# RetroESP32.net
KiCad netlist of a schematic drawn in EAGLE
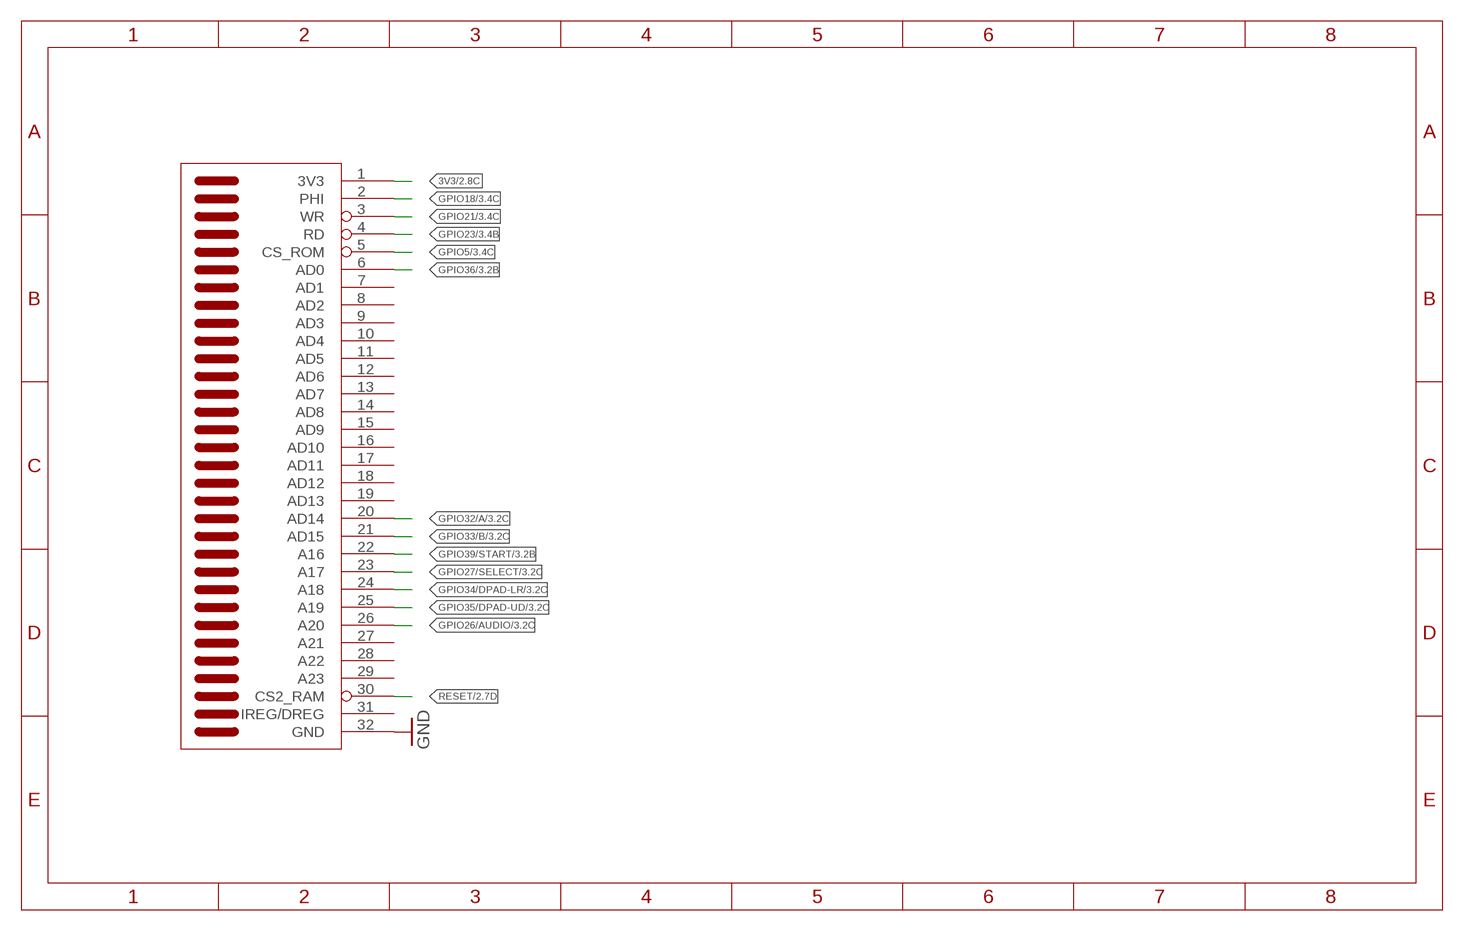
[diagram p0: schematic, sheet 1]
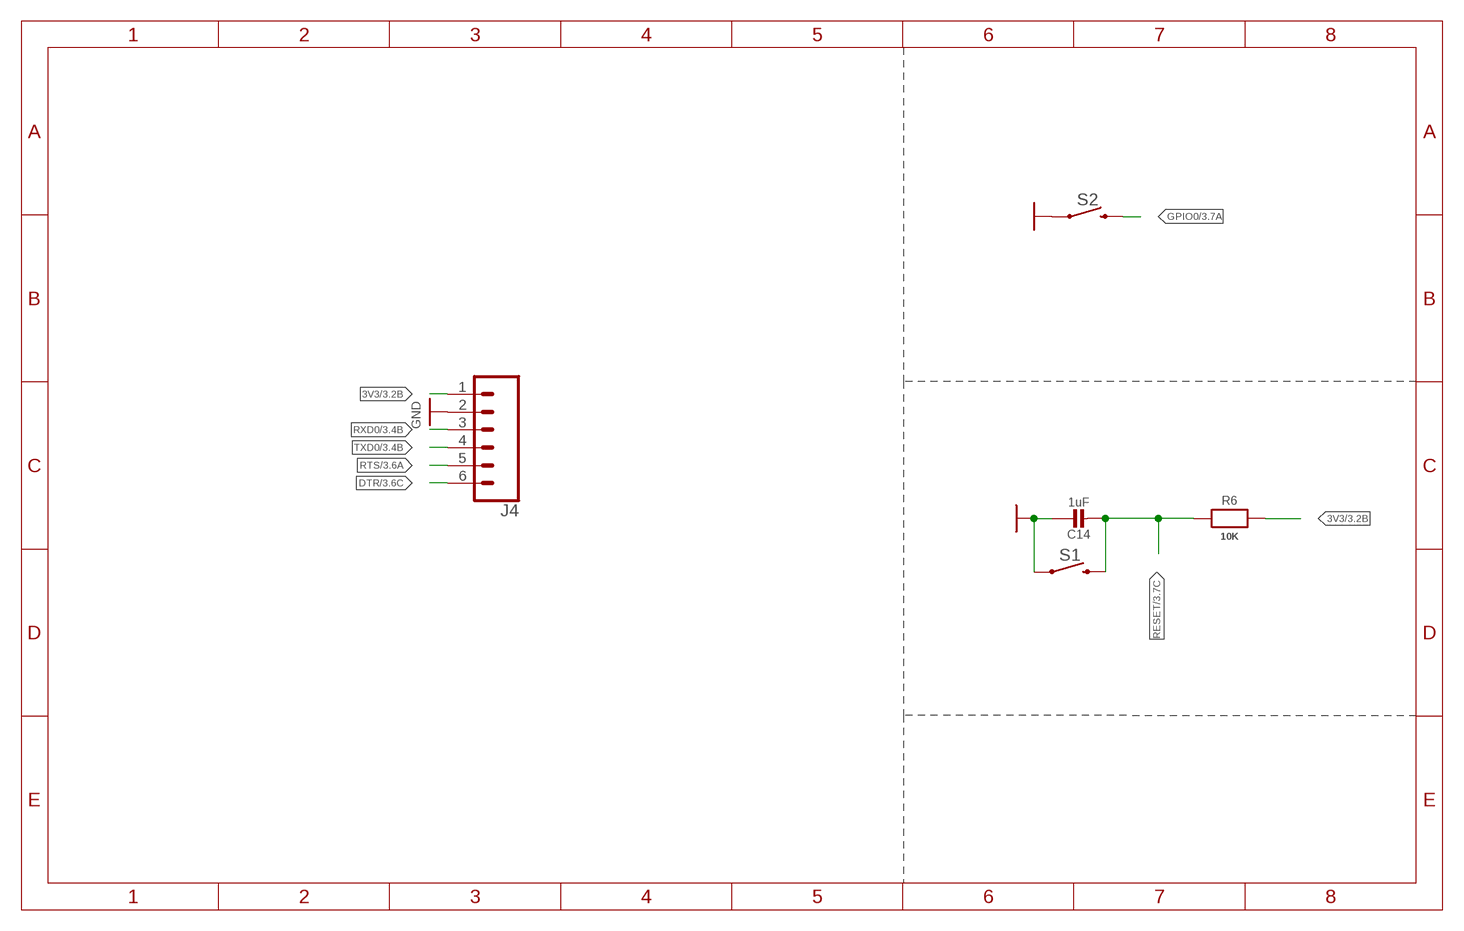
[diagram p1: schematic, sheet 2]
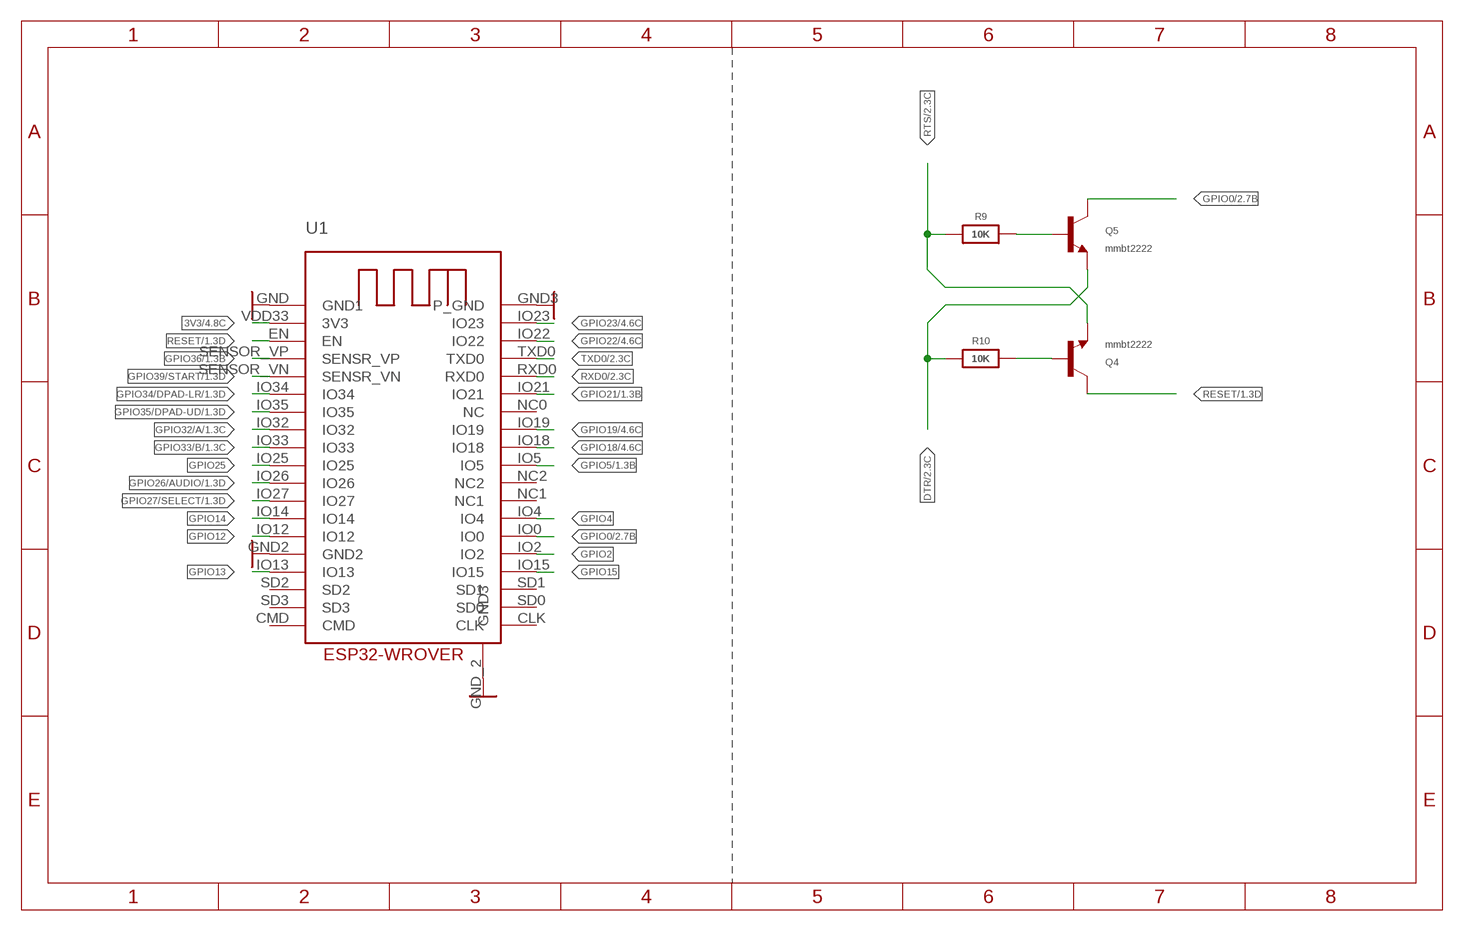
[diagram p2: schematic, sheet 3]
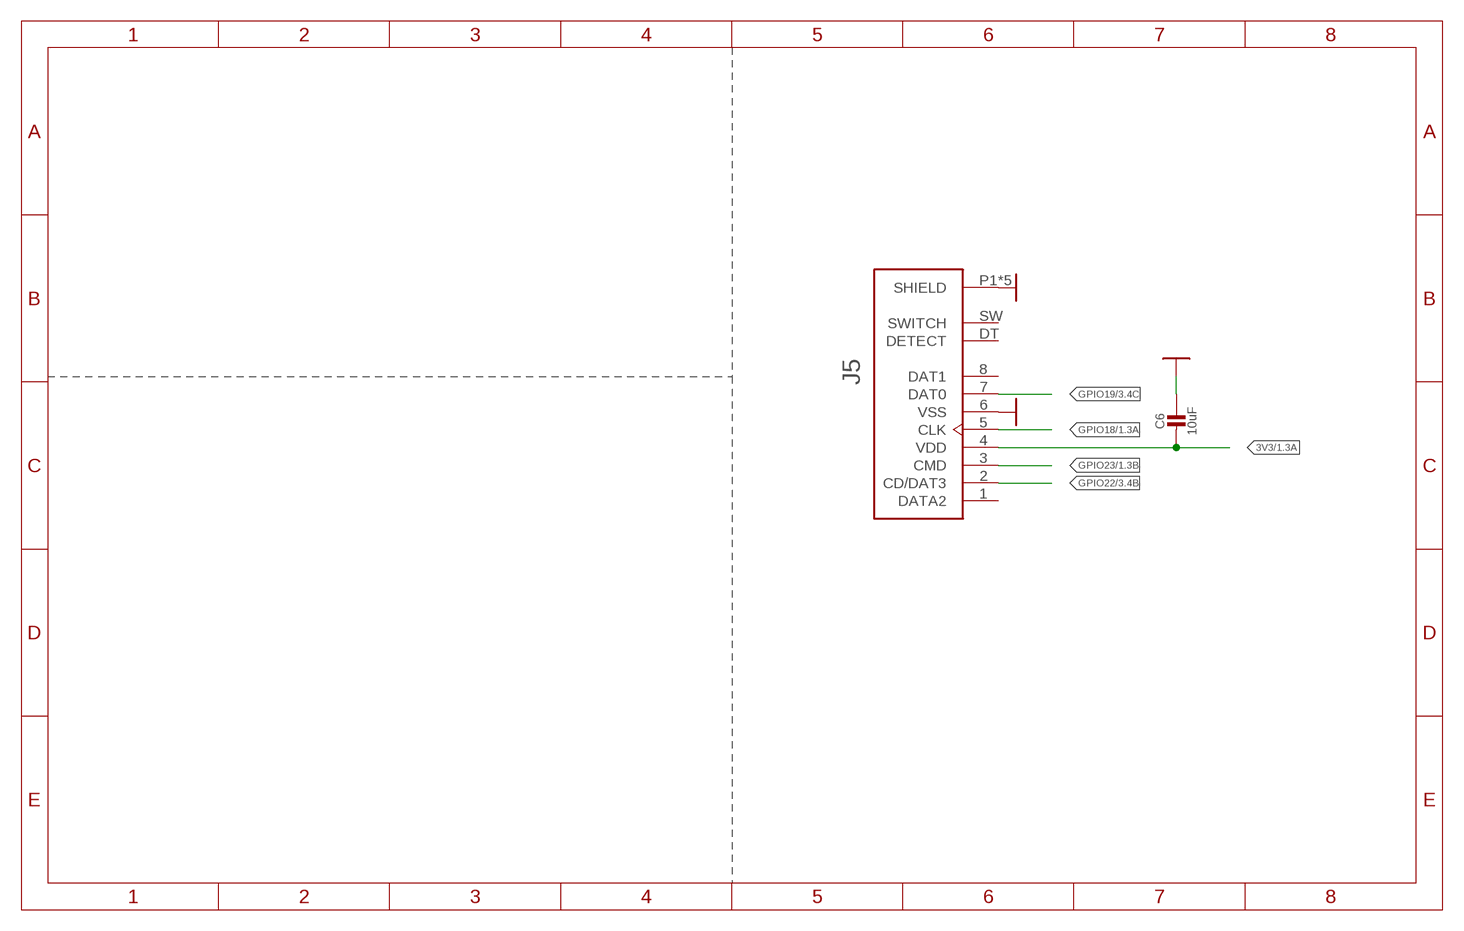
[diagram p3: schematic, sheet 4]

(export (version "E")
  (design (tool "Eeschema 10.0.6"))
  (components
    (comp (ref "C6")
      (value "10uF")
      (footprint "eagle-import:0603-MINI-CAP")
      (fields (field (name "MPN") "CL10A106MP8NNNC"))
      (libsource (lib "eagle-import") (part "CAP_CERAMIC"))
    )
    (comp (ref "J5")
      (value "503182-1852_503182-1852")
      (footprint "eagle-import:503182-1852_MOLEX_503182-1852")
      (fields
        (field (name "DIGI-KEY_PART_NUMBER") "WM12834CT-ND")
        (field (name "MF") "Molex")
        (field (name "MP") "5031821852")
      )
      (libsource (lib "eagle-import") (part "503182-1852_503182-1852"))
    )
    (comp (ref "Q4")
      (value "mmbt2222")
      (footprint "eagle-import:SOT23-3")
      (fields (field (name "MPN") "MMBT2222A-7-F"))
      (libsource (lib "eagle-import") (part "TRANSISTOR_NPNSOT23-3"))
    )
    (comp (ref "Q5")
      (value "mmbt2222")
      (footprint "eagle-import:SOT23-3")
      (fields (field (name "MPN") "MMBT2222A-7-F"))
      (libsource (lib "eagle-import") (part "TRANSISTOR_NPNSOT23-3"))
    )
    (comp (ref "R9")
      (value "10K")
      (footprint "eagle-import:0603-MINI")
      (fields (field (name "MPN") "ERJ-PA3J103V"))
      (libsource (lib "eagle-import") (part "RESISTOR0603MINI"))
    )
    (comp (ref "R10")
      (value "10K")
      (footprint "eagle-import:0603-MINI")
      (fields (field (name "MPN") "ERJ-PA3J103V"))
      (libsource (lib "eagle-import") (part "RESISTOR0603MINI"))
    )
    (comp (ref "U1")
      (value "ESP32-WROVER_ESP32-WROVER")
      (footprint "eagle-import:ESP32-WROVER_ESP32-WROVER")
      (fields (field (name "MPN") "ESP32-WROVER (16MB)"))
      (libsource (lib "eagle-import") (part "ESP32-WROVER_ESP32-WROVER"))
    )
    (comp (ref "U$2")
      (value "GBA_CARTLARGE")
      (footprint "eagle-import:GBCART")
      (libsource (lib "eagle-import") (part "GBA_CARTLARGE"))
    )
    (comp (ref "C14")
      (value "1uF")
      (footprint "eagle-import:0603-MINI-CAP")
      (fields (field (name "MPN") "CL10A105KP8NNNC"))
      (libsource (lib "eagle-import") (part "CAP_CERAMIC"))
    )
    (comp (ref "J4")
      (value "CONN_06NO_SILK_NO_POP")
      (footprint "eagle-import:1X06_NO_SILK")
      (libsource (lib "eagle-import") (part "CONN_06NO_SILK_NO_POP"))
    )
    (comp (ref "R6")
      (value "10K")
      (footprint "eagle-import:0603-MINI")
      (fields (field (name "MPN") "ERJ-PA3J103V"))
      (libsource (lib "eagle-import") (part "RESISTOR0603MINI"))
    )
    (comp (ref "S1")
      (value "SWITCHES_MOMENTARY-SWITCH-SPST-SMD-4.6X2.8MM")
      (footprint "eagle-import:SWITCHES_TACTILE_SWITCH_SMD_4.6X2.8MM")
      (fields (field (name "MPN") "KMR221GLFS"))
      (libsource (lib "eagle-import") (part "SWITCHES_MOMENTARY-SWITCH-SPST-SMD-4.6X2.8MM"))
    )
    (comp (ref "S2")
      (value "SWITCHES_MOMENTARY-SWITCH-SPST-SMD-4.6X2.8MM")
      (footprint "eagle-import:SWITCHES_TACTILE_SWITCH_SMD_4.6X2.8MM")
      (fields (field (name "MPN") "KMR221GLFS"))
      (libsource (lib "eagle-import") (part "SWITCHES_MOMENTARY-SWITCH-SPST-SMD-4.6X2.8MM"))
    )
  )
  (nets
    (net (code "1") (name "3V3") (class "Default")
      (node (ref "C6") (pin "2") (pinfunction "2_2") (pintype "passive"))
      (node (ref "J4") (pin "1") (pinfunction "1_1") (pintype "passive"))
      (node (ref "J5") (pin "4") (pinfunction "VDD_4") (pintype "power_in"))
      (node (ref "R6") (pin "2") (pinfunction "2_2") (pintype "passive"))
      (node (ref "U$2") (pin "1") (pinfunction "3V3_1") (pintype "power_in"))
      (node (ref "U1") (pin "VDD33") (pinfunction "3V3_VDD33") (pintype "bidirectional"))
    )
    (net (code "2") (name "DTR") (class "Default")
      (node (ref "J4") (pin "6") (pinfunction "6_6") (pintype "passive"))
      (node (ref "Q5") (pin "2") (pinfunction "E_2") (pintype "passive"))
      (node (ref "R10") (pin "1") (pinfunction "1_1") (pintype "passive"))
    )
    (net (code "3") (name "GND") (class "Default")
      (node (ref "C14") (pin "1") (pinfunction "1_1") (pintype "passive"))
      (node (ref "C6") (pin "1") (pinfunction "1_1") (pintype "passive"))
      (node (ref "J4") (pin "2") (pinfunction "2_2") (pintype "passive"))
      (node (ref "J5") (pin "6") (pinfunction "VSS_6") (pintype "power_in"))
      (node (ref "J5") (pin "P1") (pinfunction "SHIELD_P1") (pintype "passive"))
      (node (ref "J5") (pin "P2") (pinfunction "SHIELD_P2") (pintype "passive"))
      (node (ref "J5") (pin "P3") (pinfunction "SHIELD_P3") (pintype "passive"))
      (node (ref "J5") (pin "P4") (pinfunction "SHIELD_P4") (pintype "passive"))
      (node (ref "J5") (pin "P5") (pinfunction "SHIELD_P5") (pintype "passive"))
      (node (ref "S1") (pin "1") (pinfunction "1_1") (pintype "passive"))
      (node (ref "S1") (pin "2") (pinfunction "1_2") (pintype "passive"))
      (node (ref "S2") (pin "1") (pinfunction "1_1") (pintype "passive"))
      (node (ref "S2") (pin "2") (pinfunction "1_2") (pintype "passive"))
      (node (ref "U$2") (pin "32") (pinfunction "GND_32") (pintype "power_in"))
      (node (ref "U1") (pin "GND") (pinfunction "GND1_GND") (pintype "bidirectional"))
      (node (ref "U1") (pin "GND2") (pinfunction "GND2_GND2") (pintype "bidirectional"))
      (node (ref "U1") (pin "GND3") (pinfunction "P_GND_GND3") (pintype "bidirectional"))
      (node (ref "U1") (pin "GND_2") (pinfunction "GND3_GND_2") (pintype "bidirectional"))
    )
    (net (code "4") (name "GPIO0") (class "Default")
      (node (ref "Q5") (pin "3") (pinfunction "C_3") (pintype "passive"))
      (node (ref "S2") (pin "3") (pinfunction "2_3") (pintype "passive"))
      (node (ref "S2") (pin "4") (pinfunction "2_4") (pintype "passive"))
      (node (ref "U1") (pin "IO0") (pinfunction "IO0_IO0") (pintype "bidirectional"))
    )
    (net (code "5") (name "GPIO2") (class "Default")
      (node (ref "U1") (pin "IO2") (pinfunction "IO2_IO2") (pintype "bidirectional"))
    )
    (net (code "6") (name "GPIO4") (class "Default")
      (node (ref "U1") (pin "IO4") (pinfunction "IO4_IO4") (pintype "bidirectional"))
    )
    (net (code "7") (name "GPIO5") (class "Default")
      (node (ref "U$2") (pin "5") (pinfunction "CS_ROM_5") (pintype "output"))
      (node (ref "U1") (pin "IO5") (pinfunction "IO5_IO5") (pintype "bidirectional"))
    )
    (net (code "8") (name "GPIO12") (class "Default")
      (node (ref "U1") (pin "IO12") (pinfunction "IO12_IO12") (pintype "bidirectional"))
    )
    (net (code "9") (name "GPIO13") (class "Default")
      (node (ref "U1") (pin "IO13") (pinfunction "IO13_IO13") (pintype "bidirectional"))
    )
    (net (code "10") (name "GPIO14") (class "Default")
      (node (ref "U1") (pin "IO14") (pinfunction "IO14_IO14") (pintype "bidirectional"))
    )
    (net (code "11") (name "GPIO15") (class "Default")
      (node (ref "U1") (pin "IO15") (pinfunction "IO15_IO15") (pintype "bidirectional"))
    )
    (net (code "12") (name "GPIO18") (class "Default")
      (node (ref "J5") (pin "5") (pinfunction "CLK_5") (pintype "bidirectional"))
      (node (ref "U$2") (pin "2") (pinfunction "PHI_2") (pintype "bidirectional"))
      (node (ref "U1") (pin "IO18") (pinfunction "IO18_IO18") (pintype "bidirectional"))
    )
    (net (code "13") (name "GPIO19") (class "Default")
      (node (ref "J5") (pin "7") (pinfunction "DAT0_7") (pintype "bidirectional"))
      (node (ref "U1") (pin "IO19") (pinfunction "IO19_IO19") (pintype "bidirectional"))
    )
    (net (code "14") (name "GPIO21") (class "Default")
      (node (ref "U$2") (pin "3") (pinfunction "WR_3") (pintype "output"))
      (node (ref "U1") (pin "IO21") (pinfunction "IO21_IO21") (pintype "bidirectional"))
    )
    (net (code "15") (name "GPIO22") (class "Default")
      (node (ref "J5") (pin "2") (pinfunction "CD/DAT3_2") (pintype "bidirectional"))
      (node (ref "U1") (pin "IO22") (pinfunction "IO22_IO22") (pintype "bidirectional"))
    )
    (net (code "16") (name "GPIO23") (class "Default")
      (node (ref "J5") (pin "3") (pinfunction "CMD_3") (pintype "bidirectional"))
      (node (ref "U$2") (pin "4") (pinfunction "RD_4") (pintype "output"))
      (node (ref "U1") (pin "IO23") (pinfunction "IO23_IO23") (pintype "bidirectional"))
    )
    (net (code "17") (name "GPIO25") (class "Default")
      (node (ref "U1") (pin "IO25") (pinfunction "IO25_IO25") (pintype "bidirectional"))
    )
    (net (code "18") (name "GPIO26{slash}AUDIO") (class "Default")
      (node (ref "U$2") (pin "26") (pinfunction "A20_26") (pintype "output"))
      (node (ref "U1") (pin "IO26") (pinfunction "IO26_IO26") (pintype "bidirectional"))
    )
    (net (code "19") (name "GPIO27{slash}SELECT") (class "Default")
      (node (ref "U$2") (pin "23") (pinfunction "A17_23") (pintype "output"))
      (node (ref "U1") (pin "IO27") (pinfunction "IO27_IO27") (pintype "bidirectional"))
    )
    (net (code "20") (name "GPIO32{slash}A") (class "Default")
      (node (ref "U$2") (pin "20") (pinfunction "AD14_20") (pintype "bidirectional"))
      (node (ref "U1") (pin "IO32") (pinfunction "IO32_IO32") (pintype "bidirectional"))
    )
    (net (code "21") (name "GPIO33{slash}B") (class "Default")
      (node (ref "U$2") (pin "21") (pinfunction "AD15_21") (pintype "bidirectional"))
      (node (ref "U1") (pin "IO33") (pinfunction "IO33_IO33") (pintype "bidirectional"))
    )
    (net (code "22") (name "GPIO34{slash}DPAD-LR") (class "Default")
      (node (ref "U$2") (pin "24") (pinfunction "A18_24") (pintype "output"))
      (node (ref "U1") (pin "IO34") (pinfunction "IO34_IO34") (pintype "bidirectional"))
    )
    (net (code "23") (name "GPIO35{slash}DPAD-UD") (class "Default")
      (node (ref "U$2") (pin "25") (pinfunction "A19_25") (pintype "output"))
      (node (ref "U1") (pin "IO35") (pinfunction "IO35_IO35") (pintype "bidirectional"))
    )
    (net (code "24") (name "GPIO36") (class "Default")
      (node (ref "U$2") (pin "6") (pinfunction "AD0_6") (pintype "bidirectional"))
      (node (ref "U1") (pin "SENSOR_VP") (pinfunction "SENSR_VP_SENSOR_VP") (pintype "bidirectional"))
    )
    (net (code "25") (name "GPIO39{slash}START") (class "Default")
      (node (ref "U$2") (pin "22") (pinfunction "A16_22") (pintype "output"))
      (node (ref "U1") (pin "SENSOR_VN") (pinfunction "SENSR_VN_SENSOR_VN") (pintype "bidirectional"))
    )
    (net (code "26") (name "Net-(Q4-B)") (class "Default")
      (node (ref "Q4") (pin "1") (pinfunction "B_1") (pintype "passive"))
      (node (ref "R10") (pin "2") (pinfunction "2_2") (pintype "passive"))
    )
    (net (code "27") (name "Net-(Q5-B)") (class "Default")
      (node (ref "Q5") (pin "1") (pinfunction "B_1") (pintype "passive"))
      (node (ref "R9") (pin "2") (pinfunction "2_2") (pintype "passive"))
    )
    (net (code "28") (name "RESET") (class "Default")
      (node (ref "C14") (pin "2") (pinfunction "2_2") (pintype "passive"))
      (node (ref "Q4") (pin "3") (pinfunction "C_3") (pintype "passive"))
      (node (ref "R6") (pin "1") (pinfunction "1_1") (pintype "passive"))
      (node (ref "S1") (pin "3") (pinfunction "2_3") (pintype "passive"))
      (node (ref "S1") (pin "4") (pinfunction "2_4") (pintype "passive"))
      (node (ref "U$2") (pin "30") (pinfunction "CS2_RAM_30") (pintype "output"))
      (node (ref "U1") (pin "EN") (pinfunction "EN_EN") (pintype "bidirectional"))
    )
    (net (code "29") (name "RTS") (class "Default")
      (node (ref "J4") (pin "5") (pinfunction "5_5") (pintype "passive"))
      (node (ref "Q4") (pin "2") (pinfunction "E_2") (pintype "passive"))
      (node (ref "R9") (pin "1") (pinfunction "1_1") (pintype "passive"))
    )
    (net (code "30") (name "RXD0") (class "Default")
      (node (ref "J4") (pin "3") (pinfunction "3_3") (pintype "passive"))
      (node (ref "U1") (pin "RXD0") (pinfunction "RXD0_RXD0") (pintype "bidirectional"))
    )
    (net (code "31") (name "TXD0") (class "Default")
      (node (ref "J4") (pin "4") (pinfunction "4_4") (pintype "passive"))
      (node (ref "U1") (pin "TXD0") (pinfunction "TXD0_TXD0") (pintype "bidirectional"))
    )
    (net (code "32") (name "unconnected-(J5-DAT1-Pad8)") (class "Default")
      (node (ref "J5") (pin "8") (pinfunction "DAT1_8") (pintype "bidirectional"))
    )
    (net (code "33") (name "unconnected-(J5-DATA2-Pad1)") (class "Default")
      (node (ref "J5") (pin "1") (pinfunction "DATA2_1") (pintype "bidirectional"))
    )
    (net (code "34") (name "unconnected-(J5-DETECT-PadDT)") (class "Default")
      (node (ref "J5") (pin "DT") (pinfunction "DETECT_DT") (pintype "bidirectional"))
    )
    (net (code "35") (name "unconnected-(J5-SWITCH-PadSW)") (class "Default")
      (node (ref "J5") (pin "SW") (pinfunction "SWITCH_SW") (pintype "bidirectional"))
    )
    (net (code "36") (name "unconnected-(U$2-A21-Pad27)") (class "Default")
      (node (ref "U$2") (pin "27") (pinfunction "A21_27") (pintype "output"))
    )
    (net (code "37") (name "unconnected-(U$2-A22-Pad28)") (class "Default")
      (node (ref "U$2") (pin "28") (pinfunction "A22_28") (pintype "output"))
    )
    (net (code "38") (name "unconnected-(U$2-A23-Pad29)") (class "Default")
      (node (ref "U$2") (pin "29") (pinfunction "A23_29") (pintype "output"))
    )
    (net (code "39") (name "unconnected-(U$2-AD1-Pad7)") (class "Default")
      (node (ref "U$2") (pin "7") (pinfunction "AD1_7") (pintype "bidirectional"))
    )
    (net (code "40") (name "unconnected-(U$2-AD2-Pad8)") (class "Default")
      (node (ref "U$2") (pin "8") (pinfunction "AD2_8") (pintype "bidirectional"))
    )
    (net (code "41") (name "unconnected-(U$2-AD3-Pad9)") (class "Default")
      (node (ref "U$2") (pin "9") (pinfunction "AD3_9") (pintype "bidirectional"))
    )
    (net (code "42") (name "unconnected-(U$2-AD4-Pad10)") (class "Default")
      (node (ref "U$2") (pin "10") (pinfunction "AD4_10") (pintype "bidirectional"))
    )
    (net (code "43") (name "unconnected-(U$2-AD5-Pad11)") (class "Default")
      (node (ref "U$2") (pin "11") (pinfunction "AD5_11") (pintype "bidirectional"))
    )
    (net (code "44") (name "unconnected-(U$2-AD6-Pad12)") (class "Default")
      (node (ref "U$2") (pin "12") (pinfunction "AD6_12") (pintype "bidirectional"))
    )
    (net (code "45") (name "unconnected-(U$2-AD7-Pad13)") (class "Default")
      (node (ref "U$2") (pin "13") (pinfunction "AD7_13") (pintype "bidirectional"))
    )
    (net (code "46") (name "unconnected-(U$2-AD8-Pad14)") (class "Default")
      (node (ref "U$2") (pin "14") (pinfunction "AD8_14") (pintype "bidirectional"))
    )
    (net (code "47") (name "unconnected-(U$2-AD9-Pad15)") (class "Default")
      (node (ref "U$2") (pin "15") (pinfunction "AD9_15") (pintype "bidirectional"))
    )
    (net (code "48") (name "unconnected-(U$2-AD10-Pad16)") (class "Default")
      (node (ref "U$2") (pin "16") (pinfunction "AD10_16") (pintype "bidirectional"))
    )
    (net (code "49") (name "unconnected-(U$2-AD11-Pad17)") (class "Default")
      (node (ref "U$2") (pin "17") (pinfunction "AD11_17") (pintype "bidirectional"))
    )
    (net (code "50") (name "unconnected-(U$2-AD12-Pad18)") (class "Default")
      (node (ref "U$2") (pin "18") (pinfunction "AD12_18") (pintype "bidirectional"))
    )
    (net (code "51") (name "unconnected-(U$2-AD13-Pad19)") (class "Default")
      (node (ref "U$2") (pin "19") (pinfunction "AD13_19") (pintype "bidirectional"))
    )
    (net (code "52") (name "unconnected-(U$2-IREG{slash}DREG-Pad31)") (class "Default")
      (node (ref "U$2") (pin "31") (pinfunction "IREG/DREG_31") (pintype "input"))
    )
    (net (code "53") (name "unconnected-(U1-NC-PadNC0)") (class "Default")
      (node (ref "U1") (pin "NC0") (pinfunction "NC_NC0") (pintype "bidirectional"))
    )
    (net (code "54") (name "unconnected-(U1-PadCLK)") (class "Default")
      (node (ref "U1") (pin "CLK") (pinfunction "CLK_CLK") (pintype "bidirectional"))
    )
    (net (code "55") (name "unconnected-(U1-PadCMD)") (class "Default")
      (node (ref "U1") (pin "CMD") (pinfunction "CMD_CMD") (pintype "bidirectional"))
    )
    (net (code "56") (name "unconnected-(U1-PadNC1)") (class "Default")
      (node (ref "U1") (pin "NC1") (pinfunction "NC1_NC1") (pintype "bidirectional"))
    )
    (net (code "57") (name "unconnected-(U1-PadNC2)") (class "Default")
      (node (ref "U1") (pin "NC2") (pinfunction "NC2_NC2") (pintype "bidirectional"))
    )
    (net (code "58") (name "unconnected-(U1-PadSD0)") (class "Default")
      (node (ref "U1") (pin "SD0") (pinfunction "SD0_SD0") (pintype "bidirectional"))
    )
    (net (code "59") (name "unconnected-(U1-PadSD1)") (class "Default")
      (node (ref "U1") (pin "SD1") (pinfunction "SD1_SD1") (pintype "bidirectional"))
    )
    (net (code "60") (name "unconnected-(U1-PadSD2)") (class "Default")
      (node (ref "U1") (pin "SD2") (pinfunction "SD2_SD2") (pintype "bidirectional"))
    )
    (net (code "61") (name "unconnected-(U1-PadSD3)") (class "Default")
      (node (ref "U1") (pin "SD3") (pinfunction "SD3_SD3") (pintype "bidirectional"))
    )
  )
)
